# 10_FPGA_PWR.net
KiCad netlist of a schematic drawn in Altium Designer
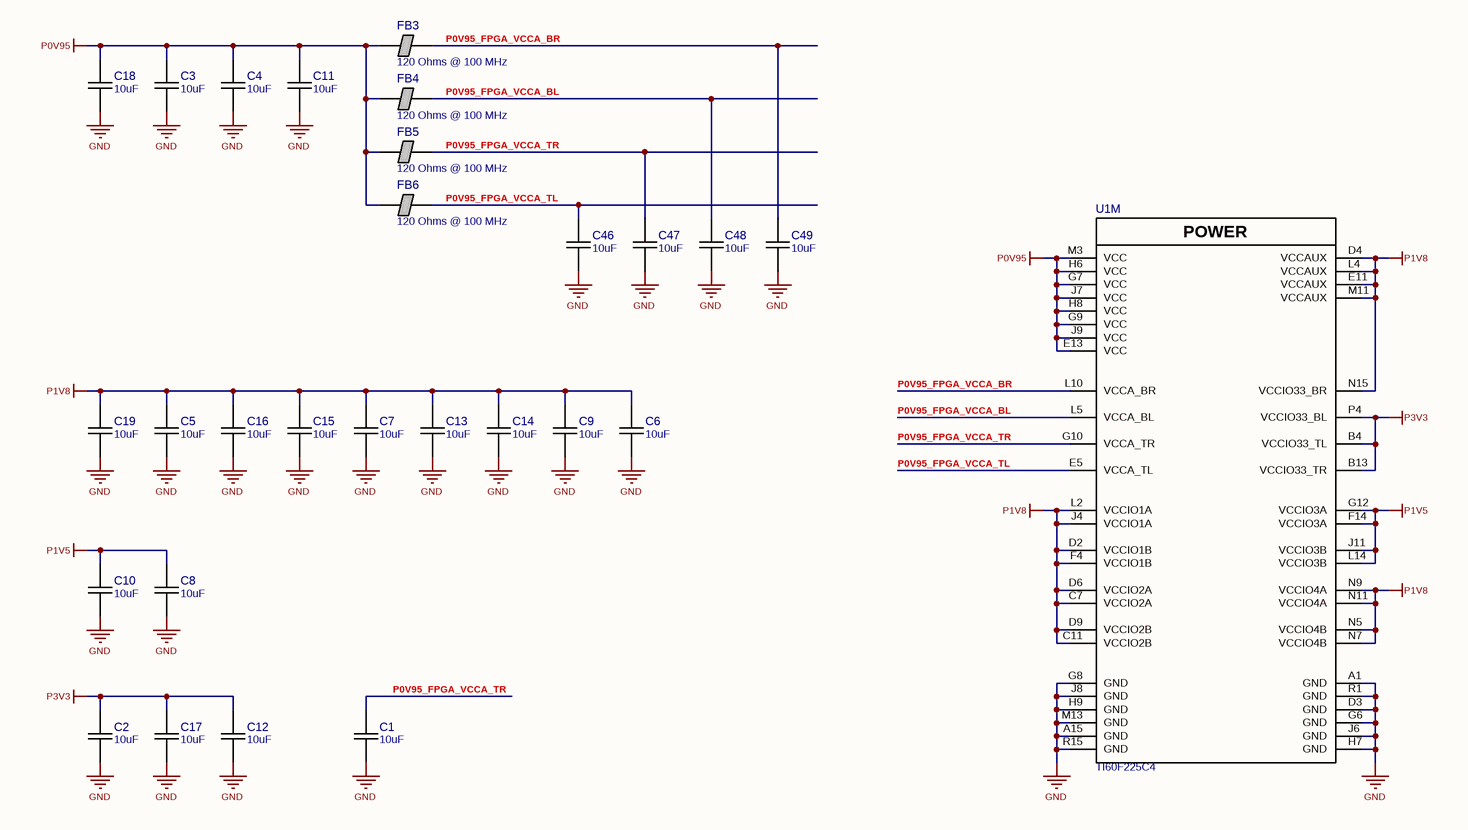
[diagram p0: 10_FPGA_PWR.SchDoc]

(export (version "E")
  (design (tool "Eeschema 10.0.6"))
  (components
    (comp (ref "C1")
      (value "10uF")
      (footprint "CAPC1005X06N")
      (description "CAP CER 10UF 6.3V X5R 0402")
      (fields (field (name "PART NUMBER") "GRM155R60J106ME47D") (field (name "VOLTAGE") "6.3V"))
      (libsource (lib "Database") (part "Capacitor"))
    )
    (comp (ref "C2")
      (value "10uF")
      (footprint "CAPC1005X06N")
      (description "CAP CER 10UF 6.3V X5R 0402")
      (fields (field (name "PART NUMBER") "GRM155R60J106ME47D") (field (name "VOLTAGE") "6.3V"))
      (libsource (lib "Database") (part "Capacitor"))
    )
    (comp (ref "C3")
      (value "10uF")
      (footprint "CAPC1005X06N")
      (description "CAP CER 10UF 6.3V X5R 0402")
      (fields (field (name "PART NUMBER") "GRM155R60J106ME47D") (field (name "VOLTAGE") "6.3V"))
      (libsource (lib "Database") (part "Capacitor"))
    )
    (comp (ref "C4")
      (value "10uF")
      (footprint "CAPC1005X06N")
      (description "CAP CER 10UF 6.3V X5R 0402")
      (fields (field (name "PART NUMBER") "GRM155R60J106ME47D") (field (name "VOLTAGE") "6.3V"))
      (libsource (lib "Database") (part "Capacitor"))
    )
    (comp (ref "C5")
      (value "10uF")
      (footprint "CAPC1005X06N")
      (description "CAP CER 10UF 6.3V X5R 0402")
      (fields (field (name "PART NUMBER") "GRM155R60J106ME47D") (field (name "VOLTAGE") "6.3V"))
      (libsource (lib "Database") (part "Capacitor"))
    )
    (comp (ref "C6")
      (value "10uF")
      (footprint "CAPC1005X06N")
      (description "CAP CER 10UF 6.3V X5R 0402")
      (fields (field (name "PART NUMBER") "GRM155R60J106ME47D") (field (name "VOLTAGE") "6.3V"))
      (libsource (lib "Database") (part "Capacitor"))
    )
    (comp (ref "C7")
      (value "10uF")
      (footprint "CAPC1005X06N")
      (description "CAP CER 10UF 6.3V X5R 0402")
      (fields (field (name "PART NUMBER") "GRM155R60J106ME47D") (field (name "VOLTAGE") "6.3V"))
      (libsource (lib "Database") (part "Capacitor"))
    )
    (comp (ref "C8")
      (value "10uF")
      (footprint "CAPC1005X06N")
      (description "CAP CER 10UF 6.3V X5R 0402")
      (fields (field (name "PART NUMBER") "GRM155R60J106ME47D") (field (name "VOLTAGE") "6.3V"))
      (libsource (lib "Database") (part "Capacitor"))
    )
    (comp (ref "C9")
      (value "10uF")
      (footprint "CAPC1005X06N")
      (description "CAP CER 10UF 6.3V X5R 0402")
      (fields (field (name "PART NUMBER") "GRM155R60J106ME47D") (field (name "VOLTAGE") "6.3V"))
      (libsource (lib "Database") (part "Capacitor"))
    )
    (comp (ref "C10")
      (value "10uF")
      (footprint "CAPC1005X06N")
      (description "CAP CER 10UF 6.3V X5R 0402")
      (fields (field (name "PART NUMBER") "GRM155R60J106ME47D") (field (name "VOLTAGE") "6.3V"))
      (libsource (lib "Database") (part "Capacitor"))
    )
    (comp (ref "C11")
      (value "10uF")
      (footprint "CAPC1005X06N")
      (description "CAP CER 10UF 6.3V X5R 0402")
      (fields (field (name "PART NUMBER") "GRM155R60J106ME47D") (field (name "VOLTAGE") "6.3V"))
      (libsource (lib "Database") (part "Capacitor"))
    )
    (comp (ref "C12")
      (value "10uF")
      (footprint "CAPC1005X06N")
      (description "CAP CER 10UF 6.3V X5R 0402")
      (fields (field (name "PART NUMBER") "GRM155R60J106ME47D") (field (name "VOLTAGE") "6.3V"))
      (libsource (lib "Database") (part "Capacitor"))
    )
    (comp (ref "C13")
      (value "10uF")
      (footprint "CAPC1005X06N")
      (description "CAP CER 10UF 6.3V X5R 0402")
      (fields (field (name "PART NUMBER") "GRM155R60J106ME47D") (field (name "VOLTAGE") "6.3V"))
      (libsource (lib "Database") (part "Capacitor"))
    )
    (comp (ref "C14")
      (value "10uF")
      (footprint "CAPC1005X06N")
      (description "CAP CER 10UF 6.3V X5R 0402")
      (fields (field (name "PART NUMBER") "GRM155R60J106ME47D") (field (name "VOLTAGE") "6.3V"))
      (libsource (lib "Database") (part "Capacitor"))
    )
    (comp (ref "C15")
      (value "10uF")
      (footprint "CAPC1005X06N")
      (description "CAP CER 10UF 6.3V X5R 0402")
      (fields (field (name "PART NUMBER") "GRM155R60J106ME47D") (field (name "VOLTAGE") "6.3V"))
      (libsource (lib "Database") (part "Capacitor"))
    )
    (comp (ref "C16")
      (value "10uF")
      (footprint "CAPC1005X06N")
      (description "CAP CER 10UF 6.3V X5R 0402")
      (fields (field (name "PART NUMBER") "GRM155R60J106ME47D") (field (name "VOLTAGE") "6.3V"))
      (libsource (lib "Database") (part "Capacitor"))
    )
    (comp (ref "C17")
      (value "10uF")
      (footprint "CAPC1005X06N")
      (description "CAP CER 10UF 6.3V X5R 0402")
      (fields (field (name "PART NUMBER") "GRM155R60J106ME47D") (field (name "VOLTAGE") "6.3V"))
      (libsource (lib "Database") (part "Capacitor"))
    )
    (comp (ref "C18")
      (value "10uF")
      (footprint "CAPC1005X06N")
      (description "CAP CER 10UF 6.3V X5R 0402")
      (fields (field (name "PART NUMBER") "GRM155R60J106ME47D") (field (name "VOLTAGE") "6.3V"))
      (libsource (lib "Database") (part "Capacitor"))
    )
    (comp (ref "C19")
      (value "10uF")
      (footprint "CAPC1005X06N")
      (description "CAP CER 10UF 6.3V X5R 0402")
      (fields (field (name "PART NUMBER") "GRM155R60J106ME47D") (field (name "VOLTAGE") "6.3V"))
      (libsource (lib "Database") (part "Capacitor"))
    )
    (comp (ref "C46")
      (value "10uF")
      (footprint "CAPC1005X06N")
      (description "CAP CER 10UF 6.3V X5R 0402")
      (fields (field (name "PART NUMBER") "GRM155R60J106ME47D") (field (name "VOLTAGE") "6.3V"))
      (libsource (lib "Database") (part "Capacitor"))
    )
    (comp (ref "C47")
      (value "10uF")
      (footprint "CAPC1005X06N")
      (description "CAP CER 10UF 6.3V X5R 0402")
      (fields (field (name "PART NUMBER") "GRM155R60J106ME47D") (field (name "VOLTAGE") "6.3V"))
      (libsource (lib "Database") (part "Capacitor"))
    )
    (comp (ref "C48")
      (value "10uF")
      (footprint "CAPC1005X06N")
      (description "CAP CER 10UF 6.3V X5R 0402")
      (fields (field (name "PART NUMBER") "GRM155R60J106ME47D") (field (name "VOLTAGE") "6.3V"))
      (libsource (lib "Database") (part "Capacitor"))
    )
    (comp (ref "C49")
      (value "10uF")
      (footprint "CAPC1005X06N")
      (description "CAP CER 10UF 6.3V X5R 0402")
      (fields (field (name "PART NUMBER") "GRM155R60J106ME47D") (field (name "VOLTAGE") "6.3V"))
      (libsource (lib "Database") (part "Capacitor"))
    )
    (comp (ref "FB3")
      (value "120 Ohms @ 100 MHz")
      (footprint "INDC1005X05N")
      (description "FERRITE BEAD 120 OHM 0402 1LN")
      (fields (field (name "PART NUMBER") "BLM15PD121SN1D"))
      (libsource (lib "Database") (part "Bead"))
    )
    (comp (ref "FB4")
      (value "120 Ohms @ 100 MHz")
      (footprint "INDC1005X05N")
      (description "FERRITE BEAD 120 OHM 0402 1LN")
      (fields (field (name "PART NUMBER") "BLM15PD121SN1D"))
      (libsource (lib "Database") (part "Bead"))
    )
    (comp (ref "FB5")
      (value "120 Ohms @ 100 MHz")
      (footprint "INDC1005X05N")
      (description "FERRITE BEAD 120 OHM 0402 1LN")
      (fields (field (name "PART NUMBER") "BLM15PD121SN1D"))
      (libsource (lib "Database") (part "Bead"))
    )
    (comp (ref "FB6")
      (value "120 Ohms @ 100 MHz")
      (footprint "INDC1005X05N")
      (description "FERRITE BEAD 120 OHM 0402 1LN")
      (fields (field (name "PART NUMBER") "BLM15PD121SN1D"))
      (libsource (lib "Database") (part "Bead"))
    )
    (comp (ref "U1")
      (value "TI60F225C4")
      (footprint "BGA225C65P15X15_1000X1000X100")
      (description "FPGA TITAN 140HSIO 4PLL 225BGA")
      (libsource (lib "Database") (part "TI60F225"))
    )
  )
  (nets
    (net (code "1") (name "/P0V95_FPGA_VCCA_BL") (class "Default")
      (node (ref "C48") (pin "2") (pinfunction "2_2") (pintype "passive"))
      (node (ref "FB4") (pin "2") (pinfunction "2_2") (pintype "passive"))
      (node (ref "U1") (pin "L5") (pinfunction "VCCA_BL_L5") (pintype "passive"))
    )
    (net (code "2") (name "/P0V95_FPGA_VCCA_BR") (class "Default")
      (node (ref "C49") (pin "2") (pinfunction "2_2") (pintype "passive"))
      (node (ref "FB3") (pin "2") (pinfunction "2_2") (pintype "passive"))
      (node (ref "U1") (pin "L10") (pinfunction "VCCA_BR_L10") (pintype "passive"))
    )
    (net (code "3") (name "/P0V95_FPGA_VCCA_TL") (class "Default")
      (node (ref "C46") (pin "2") (pinfunction "2_2") (pintype "passive"))
      (node (ref "FB6") (pin "2") (pinfunction "2_2") (pintype "passive"))
      (node (ref "U1") (pin "E5") (pinfunction "VCCA_TL_E5") (pintype "passive"))
    )
    (net (code "4") (name "/P0V95_FPGA_VCCA_TR") (class "Default")
      (node (ref "C1") (pin "2") (pinfunction "2_2") (pintype "passive"))
      (node (ref "C47") (pin "2") (pinfunction "2_2") (pintype "passive"))
      (node (ref "FB5") (pin "2") (pinfunction "2_2") (pintype "passive"))
      (node (ref "U1") (pin "G10") (pinfunction "VCCA_TR_G10") (pintype "passive"))
    )
    (net (code "5") (name "GND") (class "Default")
      (node (ref "C1") (pin "1") (pinfunction "1_1") (pintype "passive"))
      (node (ref "C10") (pin "1") (pinfunction "1_1") (pintype "passive"))
      (node (ref "C11") (pin "1") (pinfunction "1_1") (pintype "passive"))
      (node (ref "C12") (pin "1") (pinfunction "1_1") (pintype "passive"))
      (node (ref "C13") (pin "1") (pinfunction "1_1") (pintype "passive"))
      (node (ref "C14") (pin "1") (pinfunction "1_1") (pintype "passive"))
      (node (ref "C15") (pin "1") (pinfunction "1_1") (pintype "passive"))
      (node (ref "C16") (pin "1") (pinfunction "1_1") (pintype "passive"))
      (node (ref "C17") (pin "1") (pinfunction "1_1") (pintype "passive"))
      (node (ref "C18") (pin "1") (pinfunction "1_1") (pintype "passive"))
      (node (ref "C19") (pin "1") (pinfunction "1_1") (pintype "passive"))
      (node (ref "C2") (pin "1") (pinfunction "1_1") (pintype "passive"))
      (node (ref "C3") (pin "1") (pinfunction "1_1") (pintype "passive"))
      (node (ref "C4") (pin "1") (pinfunction "1_1") (pintype "passive"))
      (node (ref "C46") (pin "1") (pinfunction "1_1") (pintype "passive"))
      (node (ref "C47") (pin "1") (pinfunction "1_1") (pintype "passive"))
      (node (ref "C48") (pin "1") (pinfunction "1_1") (pintype "passive"))
      (node (ref "C49") (pin "1") (pinfunction "1_1") (pintype "passive"))
      (node (ref "C5") (pin "1") (pinfunction "1_1") (pintype "passive"))
      (node (ref "C6") (pin "1") (pinfunction "1_1") (pintype "passive"))
      (node (ref "C7") (pin "1") (pinfunction "1_1") (pintype "passive"))
      (node (ref "C8") (pin "1") (pinfunction "1_1") (pintype "passive"))
      (node (ref "C9") (pin "1") (pinfunction "1_1") (pintype "passive"))
      (node (ref "U1") (pin "A1") (pinfunction "GND_A1") (pintype "passive"))
      (node (ref "U1") (pin "A15") (pinfunction "GND_A15") (pintype "passive"))
      (node (ref "U1") (pin "D3") (pinfunction "GND_D3") (pintype "passive"))
      (node (ref "U1") (pin "G6") (pinfunction "GND_G6") (pintype "passive"))
      (node (ref "U1") (pin "G8") (pinfunction "GND_G8") (pintype "passive"))
      (node (ref "U1") (pin "H7") (pinfunction "GND_H7") (pintype "passive"))
      (node (ref "U1") (pin "H9") (pinfunction "GND_H9") (pintype "passive"))
      (node (ref "U1") (pin "J6") (pinfunction "GND_J6") (pintype "passive"))
      (node (ref "U1") (pin "J8") (pinfunction "GND_J8") (pintype "passive"))
      (node (ref "U1") (pin "M13") (pinfunction "GND_M13") (pintype "passive"))
      (node (ref "U1") (pin "R1") (pinfunction "GND_R1") (pintype "passive"))
      (node (ref "U1") (pin "R15") (pinfunction "GND_R15") (pintype "passive"))
    )
    (net (code "6") (name "P0V95") (class "Default")
      (node (ref "C11") (pin "2") (pinfunction "2_2") (pintype "passive"))
      (node (ref "C18") (pin "2") (pinfunction "2_2") (pintype "passive"))
      (node (ref "C3") (pin "2") (pinfunction "2_2") (pintype "passive"))
      (node (ref "C4") (pin "2") (pinfunction "2_2") (pintype "passive"))
      (node (ref "FB3") (pin "1") (pinfunction "1_1") (pintype "passive"))
      (node (ref "FB4") (pin "1") (pinfunction "1_1") (pintype "passive"))
      (node (ref "FB5") (pin "1") (pinfunction "1_1") (pintype "passive"))
      (node (ref "FB6") (pin "1") (pinfunction "1_1") (pintype "passive"))
      (node (ref "U1") (pin "E13") (pinfunction "VCC_E13") (pintype "passive"))
      (node (ref "U1") (pin "G7") (pinfunction "VCC_G7") (pintype "passive"))
      (node (ref "U1") (pin "G9") (pinfunction "VCC_G9") (pintype "passive"))
      (node (ref "U1") (pin "H6") (pinfunction "VCC_H6") (pintype "passive"))
      (node (ref "U1") (pin "H8") (pinfunction "VCC_H8") (pintype "passive"))
      (node (ref "U1") (pin "J7") (pinfunction "VCC_J7") (pintype "passive"))
      (node (ref "U1") (pin "J9") (pinfunction "VCC_J9") (pintype "passive"))
      (node (ref "U1") (pin "M3") (pinfunction "VCC_M3") (pintype "passive"))
    )
    (net (code "7") (name "P1V5") (class "Default")
      (node (ref "C10") (pin "2") (pinfunction "2_2") (pintype "passive"))
      (node (ref "C8") (pin "2") (pinfunction "2_2") (pintype "passive"))
      (node (ref "U1") (pin "F14") (pinfunction "VCCIO3A_F14") (pintype "passive"))
      (node (ref "U1") (pin "G12") (pinfunction "VCCIO3A_G12") (pintype "passive"))
      (node (ref "U1") (pin "J11") (pinfunction "VCCIO3B_J11") (pintype "passive"))
      (node (ref "U1") (pin "L14") (pinfunction "VCCIO3B_L14") (pintype "passive"))
    )
    (net (code "8") (name "P1V8") (class "Default")
      (node (ref "C13") (pin "2") (pinfunction "2_2") (pintype "passive"))
      (node (ref "C14") (pin "2") (pinfunction "2_2") (pintype "passive"))
      (node (ref "C15") (pin "2") (pinfunction "2_2") (pintype "passive"))
      (node (ref "C16") (pin "2") (pinfunction "2_2") (pintype "passive"))
      (node (ref "C19") (pin "2") (pinfunction "2_2") (pintype "passive"))
      (node (ref "C5") (pin "2") (pinfunction "2_2") (pintype "passive"))
      (node (ref "C6") (pin "2") (pinfunction "2_2") (pintype "passive"))
      (node (ref "C7") (pin "2") (pinfunction "2_2") (pintype "passive"))
      (node (ref "C9") (pin "2") (pinfunction "2_2") (pintype "passive"))
      (node (ref "U1") (pin "C11") (pinfunction "VCCIO2B_C11") (pintype "passive"))
      (node (ref "U1") (pin "C7") (pinfunction "VCCIO2A_C7") (pintype "passive"))
      (node (ref "U1") (pin "D2") (pinfunction "VCCIO1B_D2") (pintype "passive"))
      (node (ref "U1") (pin "D4") (pinfunction "VCCAUX_D4") (pintype "passive"))
      (node (ref "U1") (pin "D6") (pinfunction "VCCIO2A_D6") (pintype "passive"))
      (node (ref "U1") (pin "D9") (pinfunction "VCCIO2B_D9") (pintype "passive"))
      (node (ref "U1") (pin "E11") (pinfunction "VCCAUX_E11") (pintype "passive"))
      (node (ref "U1") (pin "F4") (pinfunction "VCCIO1B_F4") (pintype "passive"))
      (node (ref "U1") (pin "J4") (pinfunction "VCCIO1A_J4") (pintype "passive"))
      (node (ref "U1") (pin "L2") (pinfunction "VCCIO1A_L2") (pintype "passive"))
      (node (ref "U1") (pin "L4") (pinfunction "VCCAUX_L4") (pintype "passive"))
      (node (ref "U1") (pin "M11") (pinfunction "VCCAUX_M11") (pintype "passive"))
      (node (ref "U1") (pin "N11") (pinfunction "VCCIO4A_N11") (pintype "passive"))
      (node (ref "U1") (pin "N15") (pinfunction "VCCIO33_BR_N15") (pintype "passive"))
      (node (ref "U1") (pin "N5") (pinfunction "VCCIO4B_N5") (pintype "passive"))
      (node (ref "U1") (pin "N7") (pinfunction "VCCIO4B_N7") (pintype "passive"))
      (node (ref "U1") (pin "N9") (pinfunction "VCCIO4A_N9") (pintype "passive"))
    )
    (net (code "9") (name "P3V3") (class "Default")
      (node (ref "C12") (pin "2") (pinfunction "2_2") (pintype "passive"))
      (node (ref "C17") (pin "2") (pinfunction "2_2") (pintype "passive"))
      (node (ref "C2") (pin "2") (pinfunction "2_2") (pintype "passive"))
      (node (ref "U1") (pin "B13") (pinfunction "VCCIO33_TR_B13") (pintype "passive"))
      (node (ref "U1") (pin "B4") (pinfunction "VCCIO33_TL_B4") (pintype "passive"))
      (node (ref "U1") (pin "P4") (pinfunction "VCCIO33_BL_P4") (pintype "passive"))
    )
  )
)
